# USB.net
KiCad netlist of a schematic drawn in Altium Designer
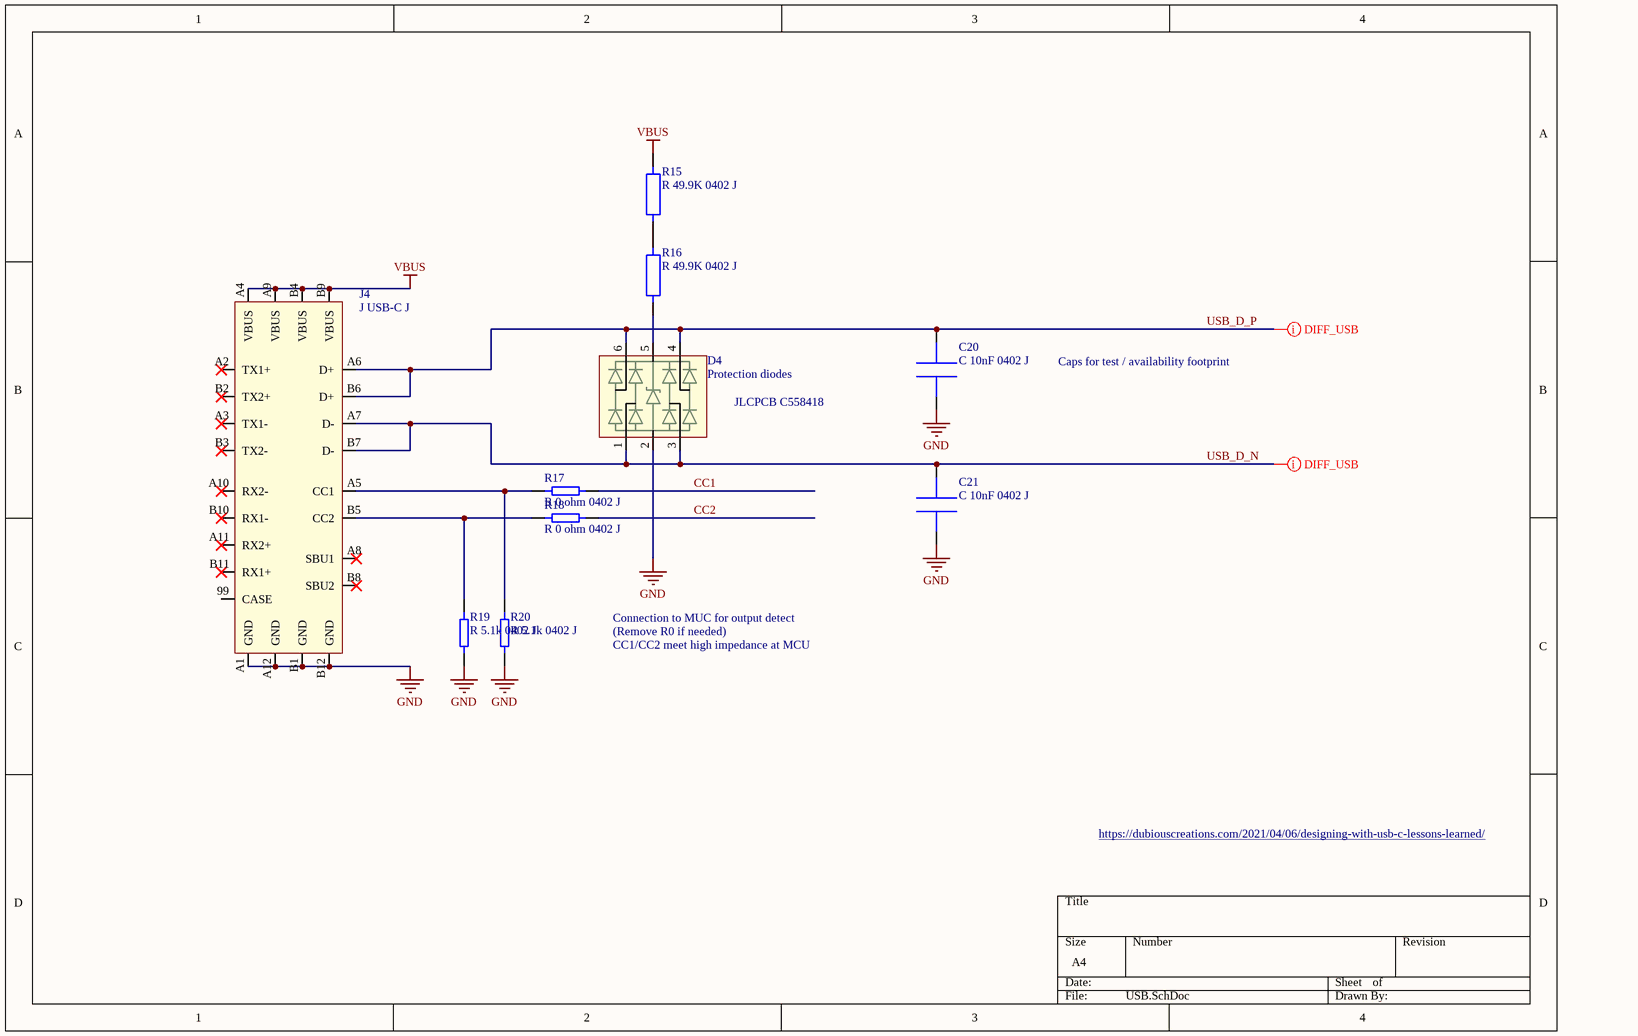
[diagram p0: USB.SchDoc]

(export (version "E")
  (design (tool "Eeschema 10.0.6"))
  (components
    (comp (ref "C20")
      (value "C 10nF 0402 J")
      (footprint "C0402")
      (description "Ceramic capacitor SMD-0402 10nF /50V X7R# K +-10%, Samsung, RoHS CL05B103KB5NNNC")
      (fields
        (field (name "MANUFACTURER") "Samsung")
        (field (name "MANUFACTURER PART NUMBER") "CL05B103KB5NNNC")
      )
      (libsource (lib "Schlib1") (part "C 10nF 0402 J"))
    )
    (comp (ref "C21")
      (value "C 10nF 0402 J")
      (footprint "C0402")
      (description "Ceramic capacitor SMD-0402 10nF /50V X7R# K +-10%, Samsung, RoHS CL05B103KB5NNNC")
      (fields
        (field (name "MANUFACTURER") "Samsung")
        (field (name "MANUFACTURER PART NUMBER") "CL05B103KB5NNNC")
      )
      (libsource (lib "Schlib1") (part "C 10nF 0402 J"))
    )
    (comp (ref "D4")
      (value "Protection diodes")
      (footprint "SOT23-SRV05")
      (description "SEMTECH - SRV05-4.TCT - ESD Protection Device, TVS, 17.5 V, SOT-23, 6 Pins, 5 V, 300 W")
      (fields (field (name "MANUFACTURER") "Semtech") (field (name "MANUFACTURER PART NUMBER") "SRV05-4.TCT"))
      (libsource (lib "Schlib1") (part "D SRV05-4.TCT"))
    )
    (comp (ref "J4")
      (value "J USB-C J")
      (footprint "MOLEX USB-C 1054500101")
      (description "Conn USB 3.1 Type C F 24 POS Solder RA SMD 24 Terminal 1 Port USB 3.1 T/R 105450-0101")
      (fields (field (name "MANUFACTURER") "Molex") (field (name "MANUFACTURER PART NUMBER") "105450-0101"))
      (libsource (lib "Schlib1") (part "J USB-C J"))
    )
    (comp (ref "R15")
      (value "R 49.9K 0402 J")
      (footprint "R0402")
      (fields
        (field (name "MANUFACTURER") "Yageo")
        (field (name "MANUFACTURER PART NUMBER") "RC0402FR-0749K9L")
        (field (name "TOLERANCE") "1%")
      )
      (libsource (lib "Schlib1") (part "R 49.9K 0402 J"))
    )
    (comp (ref "R16")
      (value "R 49.9K 0402 J")
      (footprint "R0402")
      (fields
        (field (name "MANUFACTURER") "Yageo")
        (field (name "MANUFACTURER PART NUMBER") "RC0402FR-0749K9L")
        (field (name "TOLERANCE") "1%")
      )
      (libsource (lib "Schlib1") (part "R 49.9K 0402 J"))
    )
    (comp (ref "R17")
      (value "R 0 ohm 0402 J")
      (footprint "R0402")
      (description "RC Series 0402 0.063 W 0 Ohm Jumper Surface Mount Thick Film Chip Resistor RC0402FR-070RL")
      (fields
        (field (name "MANUFACTURER") "Yageo")
        (field (name "MANUFACTURER PART NUMBER") "RC0402FR-070RL")
      )
      (libsource (lib "Schlib1") (part "R 0 ohm 0402 J"))
    )
    (comp (ref "R18")
      (value "R 0 ohm 0402 J")
      (footprint "R0402")
      (description "RC Series 0402 0.063 W 0 Ohm Jumper Surface Mount Thick Film Chip Resistor RC0402FR-070RL")
      (fields
        (field (name "MANUFACTURER") "Yageo")
        (field (name "MANUFACTURER PART NUMBER") "RC0402FR-070RL")
      )
      (libsource (lib "Schlib1") (part "R 0 ohm 0402 J"))
    )
    (comp (ref "R19")
      (value "R 5.1k 0402 J")
      (footprint "R0402")
      (fields
        (field (name "MANUFACTURER") "Yageo")
        (field (name "MANUFACTURER PART NUMBER") "RC0402FR-075K1L")
        (field (name "TOLERANCE") "1%")
      )
      (libsource (lib "Schlib1") (part "R 5.1k 0402 J"))
    )
    (comp (ref "R20")
      (value "R 5.1k 0402 J")
      (footprint "R0402")
      (fields
        (field (name "MANUFACTURER") "Yageo")
        (field (name "MANUFACTURER PART NUMBER") "RC0402FR-075K1L")
        (field (name "TOLERANCE") "1%")
      )
      (libsource (lib "Schlib1") (part "R 5.1k 0402 J"))
    )
  )
  (nets
    (net (code "1") (name "/CC1") (class "Default")
      (node (ref "R17") (pin "2") (pinfunction "2_2") (pintype "passive"))
    )
    (net (code "2") (name "/CC2") (class "Default")
      (node (ref "R18") (pin "2") (pinfunction "2_2") (pintype "passive"))
    )
    (net (code "3") (name "/USB_D_N") (class "Default")
      (node (ref "C21") (pin "2") (pinfunction "2_2") (pintype "passive"))
      (node (ref "D4") (pin "1") (pinfunction "1_1") (pintype "passive"))
      (node (ref "D4") (pin "3") (pinfunction "3_3") (pintype "passive"))
      (node (ref "J4") (pin "A7") (pinfunction "D-_A7") (pintype "passive"))
      (node (ref "J4") (pin "B7") (pinfunction "D-_B7") (pintype "passive"))
    )
    (net (code "4") (name "/USB_D_P") (class "Default")
      (node (ref "C20") (pin "2") (pinfunction "2_2") (pintype "passive"))
      (node (ref "D4") (pin "4") (pinfunction "4_4") (pintype "passive"))
      (node (ref "D4") (pin "6") (pinfunction "6_6") (pintype "passive"))
      (node (ref "J4") (pin "A6") (pinfunction "D+_A6") (pintype "passive"))
      (node (ref "J4") (pin "B6") (pinfunction "D+_B6") (pintype "passive"))
    )
    (net (code "5") (name "GND") (class "Default")
      (node (ref "C20") (pin "1") (pinfunction "1_1") (pintype "passive"))
      (node (ref "C21") (pin "1") (pinfunction "1_1") (pintype "passive"))
      (node (ref "D4") (pin "2") (pinfunction "2_2") (pintype "passive"))
      (node (ref "J4") (pin "A1") (pinfunction "GND_A1") (pintype "power_in"))
      (node (ref "J4") (pin "A12") (pinfunction "GND_A12") (pintype "power_in"))
      (node (ref "J4") (pin "B1") (pinfunction "GND_B1") (pintype "power_in"))
      (node (ref "J4") (pin "B12") (pinfunction "GND_B12") (pintype "power_in"))
      (node (ref "R19") (pin "1") (pinfunction "1_1") (pintype "passive"))
      (node (ref "R20") (pin "1") (pinfunction "1_1") (pintype "passive"))
    )
    (net (code "6") (name "Net-(D4-Pad5)") (class "Default")
      (node (ref "D4") (pin "5") (pinfunction "5_5") (pintype "passive"))
      (node (ref "R16") (pin "1") (pinfunction "1_1") (pintype "passive"))
    )
    (net (code "7") (name "Net-(J4-CC1)") (class "Default")
      (node (ref "J4") (pin "A5") (pinfunction "CC1_A5") (pintype "passive"))
      (node (ref "R17") (pin "1") (pinfunction "1_1") (pintype "passive"))
      (node (ref "R20") (pin "2") (pinfunction "2_2") (pintype "passive"))
    )
    (net (code "8") (name "Net-(J4-CC2)") (class "Default")
      (node (ref "J4") (pin "B5") (pinfunction "CC2_B5") (pintype "passive"))
      (node (ref "R18") (pin "1") (pinfunction "1_1") (pintype "passive"))
      (node (ref "R19") (pin "2") (pinfunction "2_2") (pintype "passive"))
    )
    (net (code "9") (name "Net-(R15-Pad1)") (class "Default")
      (node (ref "R15") (pin "1") (pinfunction "1_1") (pintype "passive"))
      (node (ref "R16") (pin "2") (pinfunction "2_2") (pintype "passive"))
    )
    (net (code "10") (name "VBUS") (class "Default")
      (node (ref "J4") (pin "A4") (pinfunction "VBUS_A4") (pintype "power_in"))
      (node (ref "J4") (pin "A9") (pinfunction "VBUS_A9") (pintype "power_in"))
      (node (ref "J4") (pin "B4") (pinfunction "VBUS_B4") (pintype "power_in"))
      (node (ref "J4") (pin "B9") (pinfunction "VBUS_B9") (pintype "passive"))
      (node (ref "R15") (pin "2") (pinfunction "2_2") (pintype "passive"))
    )
    (net (code "11") (name "unconnected-(J4-CASE-Pad99)") (class "Default")
      (node (ref "J4") (pin "99") (pinfunction "CASE_99") (pintype "passive"))
    )
    (net (code "12") (name "unconnected-(J4-RX1+-PadB11)") (class "Default")
      (node (ref "J4") (pin "B11") (pinfunction "RX1+_B11") (pintype "passive+no_connect"))
    )
    (net (code "13") (name "unconnected-(J4-RX1--PadB10)") (class "Default")
      (node (ref "J4") (pin "B10") (pinfunction "RX1-_B10") (pintype "passive+no_connect"))
    )
    (net (code "14") (name "unconnected-(J4-RX2+-PadA11)") (class "Default")
      (node (ref "J4") (pin "A11") (pinfunction "RX2+_A11") (pintype "passive+no_connect"))
    )
    (net (code "15") (name "unconnected-(J4-RX2--PadA10)") (class "Default")
      (node (ref "J4") (pin "A10") (pinfunction "RX2-_A10") (pintype "passive+no_connect"))
    )
    (net (code "16") (name "unconnected-(J4-SBU1-PadA8)") (class "Default")
      (node (ref "J4") (pin "A8") (pinfunction "SBU1_A8") (pintype "passive+no_connect"))
    )
    (net (code "17") (name "unconnected-(J4-SBU2-PadB8)") (class "Default")
      (node (ref "J4") (pin "B8") (pinfunction "SBU2_B8") (pintype "passive+no_connect"))
    )
    (net (code "18") (name "unconnected-(J4-TX1+-PadA2)") (class "Default")
      (node (ref "J4") (pin "A2") (pinfunction "TX1+_A2") (pintype "passive+no_connect"))
    )
    (net (code "19") (name "unconnected-(J4-TX1--PadA3)") (class "Default")
      (node (ref "J4") (pin "A3") (pinfunction "TX1-_A3") (pintype "passive+no_connect"))
    )
    (net (code "20") (name "unconnected-(J4-TX2+-PadB2)") (class "Default")
      (node (ref "J4") (pin "B2") (pinfunction "TX2+_B2") (pintype "passive+no_connect"))
    )
    (net (code "21") (name "unconnected-(J4-TX2--PadB3)") (class "Default")
      (node (ref "J4") (pin "B3") (pinfunction "TX2-_B3") (pintype "passive+no_connect"))
    )
  )
)
